# STM32H730_PINOUT.net
KiCad netlist of a schematic drawn in Altium Designer
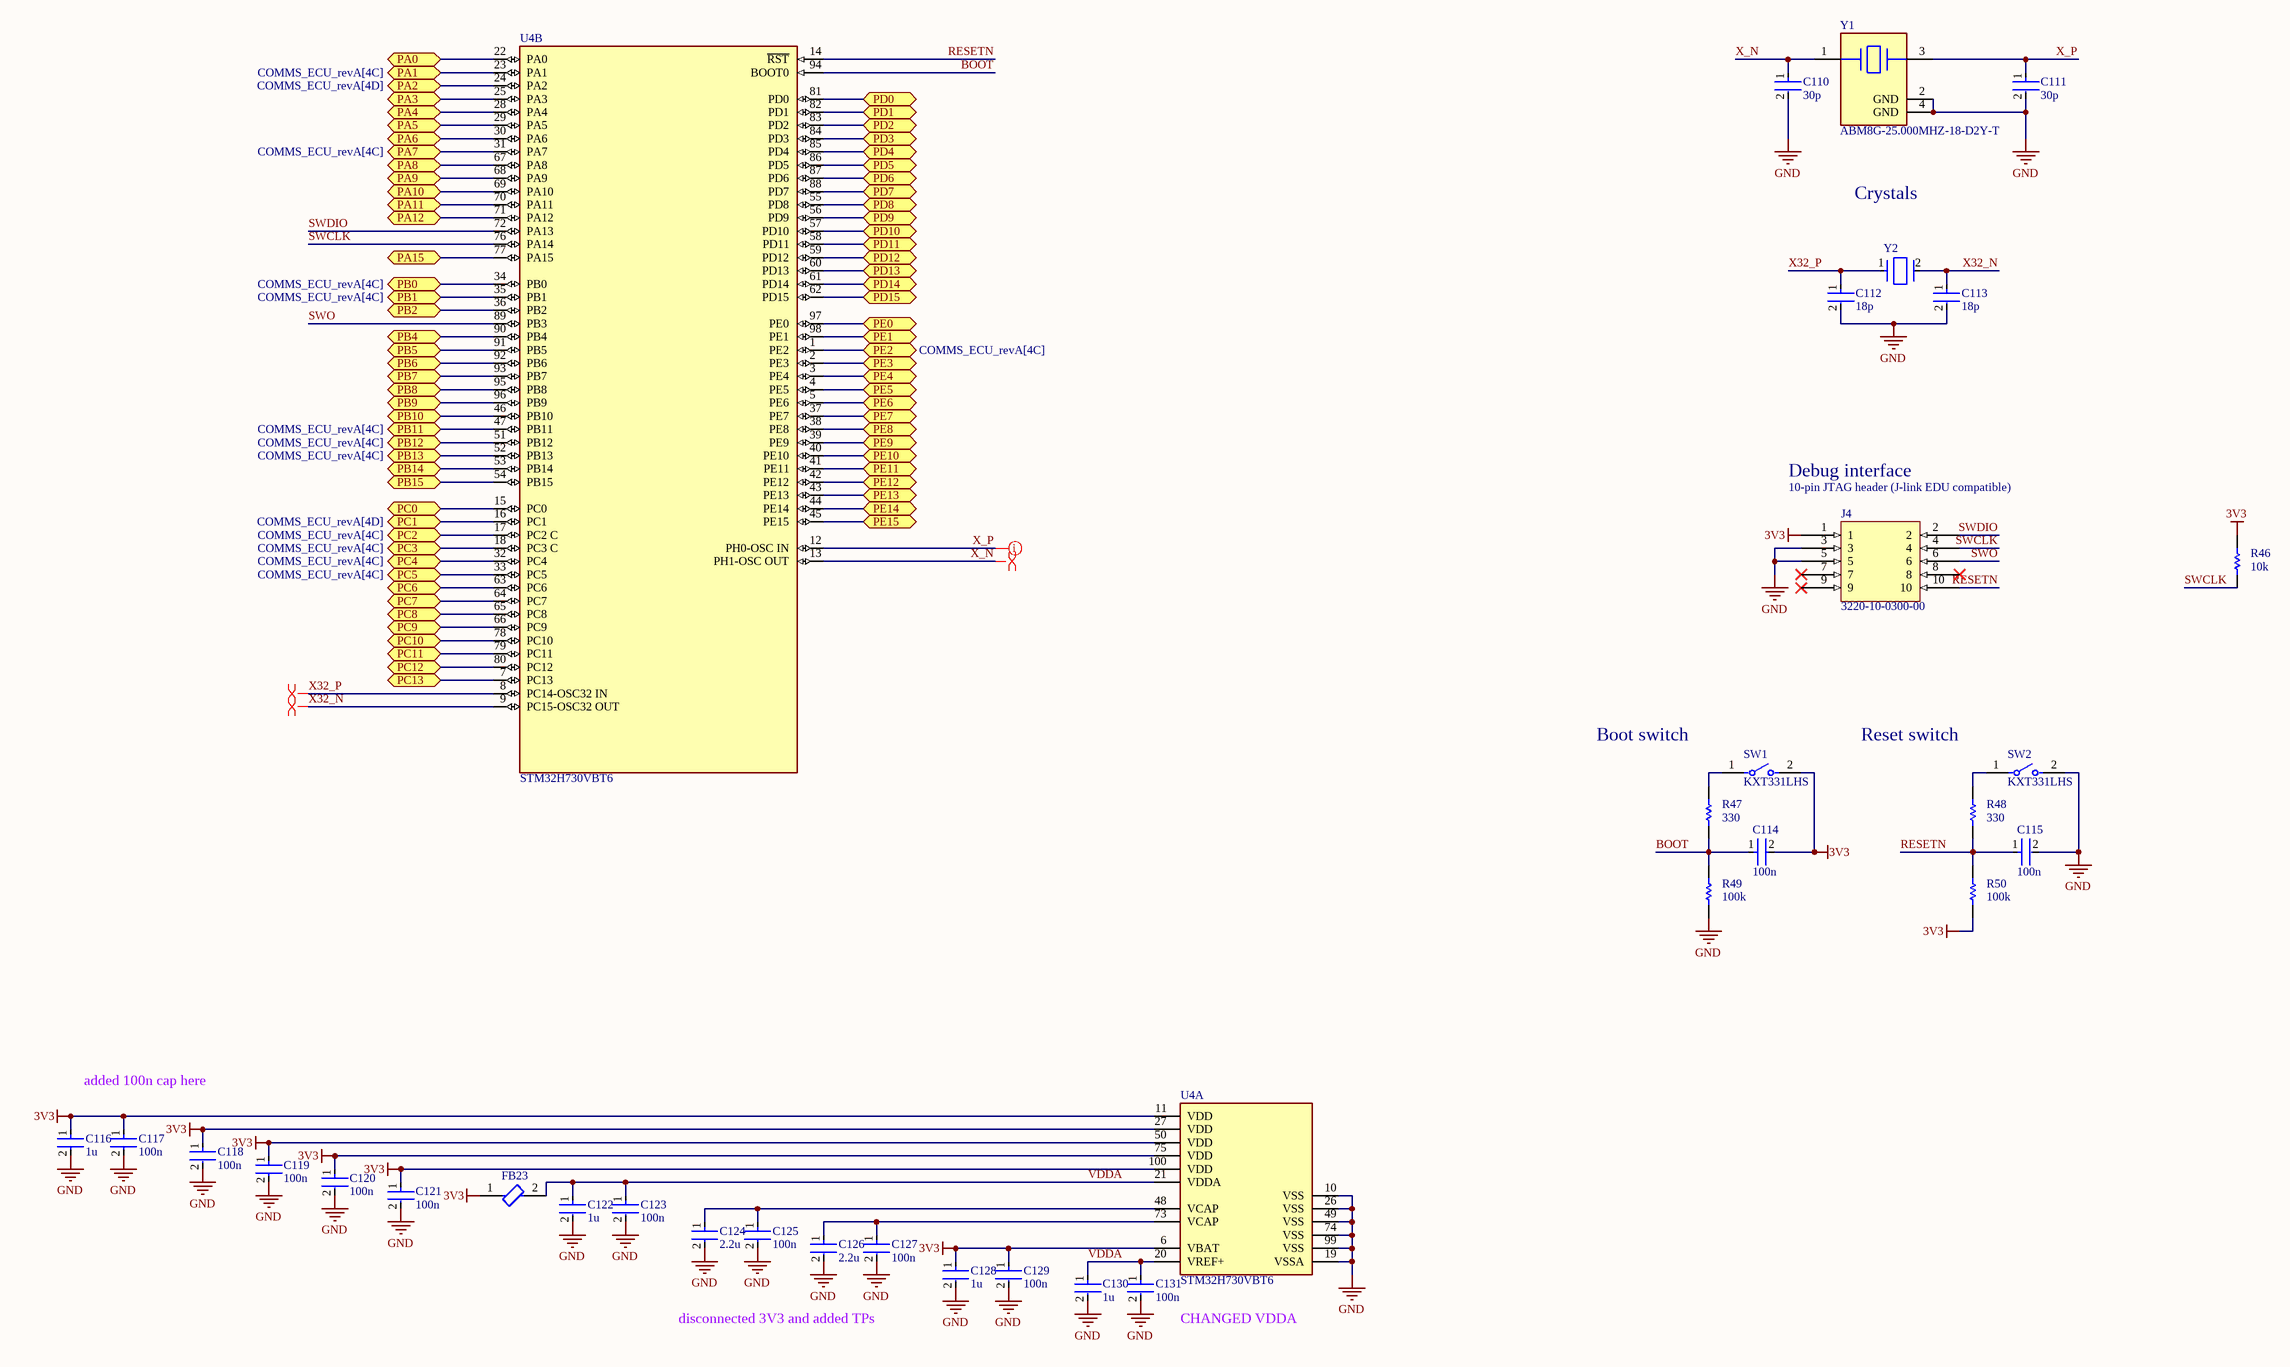
[diagram p0: STM32H730_PINOUT.SchDoc]

(export (version "E")
  (design (tool "Eeschema 10.0.6"))
  (components
    (comp (ref "C110")
      (value "30p")
      (footprint "FP-0402-L_1_0_0_05-W_0_5-IPC_A")
      (description "LARGE PADS, 0402 CAP, CHANGE COMMENT TO MATCH REAL P/N")
      (libsource (lib "Space Concordia") (part "b4654b650e69147ec39a6b967a45e02"))
    )
    (comp (ref "C111")
      (value "30p")
      (footprint "FP-0402-L_1_0_0_05-W_0_5-IPC_A")
      (description "LARGE PADS, 0402 CAP, CHANGE COMMENT TO MATCH REAL P/N")
      (libsource (lib "Space Concordia") (part "b4654b650e69147ec39a6b967a45e02"))
    )
    (comp (ref "C112")
      (value "18p")
      (footprint "FP-0402-L_1_0_0_05-W_0_5-IPC_A")
      (description "LARGE PADS, 0402 CAP, CHANGE COMMENT TO MATCH REAL P/N")
      (libsource (lib "Space Concordia") (part "b4654b650e69147ec39a6b967a45e02"))
    )
    (comp (ref "C113")
      (value "18p")
      (footprint "FP-0402-L_1_0_0_05-W_0_5-IPC_A")
      (description "LARGE PADS, 0402 CAP, CHANGE COMMENT TO MATCH REAL P/N")
      (libsource (lib "Space Concordia") (part "b4654b650e69147ec39a6b967a45e02"))
    )
    (comp (ref "C114")
      (value "100n")
      (footprint "FP-0402-L_1_0_0_05-W_0_5-IPC_A")
      (description "LARGE PADS, 0402 CAP, CHANGE COMMENT TO MATCH REAL P/N")
      (libsource (lib "Space Concordia") (part "b4654b650e69147ec39a6b967a45e02"))
    )
    (comp (ref "C115")
      (value "100n")
      (footprint "FP-0402-L_1_0_0_05-W_0_5-IPC_A")
      (description "LARGE PADS, 0402 CAP, CHANGE COMMENT TO MATCH REAL P/N")
      (libsource (lib "Space Concordia") (part "b4654b650e69147ec39a6b967a45e02"))
    )
    (comp (ref "C116")
      (value "1u")
      (footprint "FP-0402-L_1_0_0_05-W_0_5-IPC_A")
      (description "LARGE PADS, 0402 CAP, CHANGE COMMENT TO MATCH REAL P/N")
      (libsource (lib "Space Concordia") (part "b4654b650e69147ec39a6b967a45e02"))
    )
    (comp (ref "C117")
      (value "100n")
      (footprint "FP-0402-L_1_0_0_05-W_0_5-IPC_A")
      (description "LARGE PADS, 0402 CAP, CHANGE COMMENT TO MATCH REAL P/N")
      (libsource (lib "Space Concordia") (part "b4654b650e69147ec39a6b967a45e02"))
    )
    (comp (ref "C118")
      (value "100n")
      (footprint "FP-0402-L_1_0_0_05-W_0_5-IPC_A")
      (description "LARGE PADS, 0402 CAP, CHANGE COMMENT TO MATCH REAL P/N")
      (libsource (lib "Space Concordia") (part "b4654b650e69147ec39a6b967a45e02"))
    )
    (comp (ref "C119")
      (value "100n")
      (footprint "FP-0402-L_1_0_0_05-W_0_5-IPC_A")
      (description "LARGE PADS, 0402 CAP, CHANGE COMMENT TO MATCH REAL P/N")
      (libsource (lib "Space Concordia") (part "b4654b650e69147ec39a6b967a45e02"))
    )
    (comp (ref "C120")
      (value "100n")
      (footprint "FP-0402-L_1_0_0_05-W_0_5-IPC_A")
      (description "LARGE PADS, 0402 CAP, CHANGE COMMENT TO MATCH REAL P/N")
      (libsource (lib "Space Concordia") (part "b4654b650e69147ec39a6b967a45e02"))
    )
    (comp (ref "C121")
      (value "100n")
      (footprint "FP-0402-L_1_0_0_05-W_0_5-IPC_A")
      (description "LARGE PADS, 0402 CAP, CHANGE COMMENT TO MATCH REAL P/N")
      (libsource (lib "Space Concordia") (part "b4654b650e69147ec39a6b967a45e02"))
    )
    (comp (ref "C122")
      (value "1u")
      (footprint "FP-0402-L_1_0_0_05-W_0_5-IPC_A")
      (description "LARGE PADS, 0402 CAP, CHANGE COMMENT TO MATCH REAL P/N")
      (libsource (lib "Space Concordia") (part "b4654b650e69147ec39a6b967a45e02"))
    )
    (comp (ref "C123")
      (value "100n")
      (footprint "FP-0402-L_1_0_0_05-W_0_5-IPC_A")
      (description "LARGE PADS, 0402 CAP, CHANGE COMMENT TO MATCH REAL P/N")
      (libsource (lib "Space Concordia") (part "b4654b650e69147ec39a6b967a45e02"))
    )
    (comp (ref "C124")
      (value "2.2u")
      (footprint "FP-0402-L_1_0_0_05-W_0_5-IPC_A")
      (description "LARGE PADS, 0402 CAP, CHANGE COMMENT TO MATCH REAL P/N")
      (libsource (lib "Space Concordia") (part "b4654b650e69147ec39a6b967a45e02"))
    )
    (comp (ref "C125")
      (value "100n")
      (footprint "FP-0402-L_1_0_0_05-W_0_5-IPC_A")
      (description "LARGE PADS, 0402 CAP, CHANGE COMMENT TO MATCH REAL P/N")
      (libsource (lib "Space Concordia") (part "b4654b650e69147ec39a6b967a45e02"))
    )
    (comp (ref "C126")
      (value "2.2u")
      (footprint "FP-0402-L_1_0_0_05-W_0_5-IPC_A")
      (description "LARGE PADS, 0402 CAP, CHANGE COMMENT TO MATCH REAL P/N")
      (libsource (lib "Space Concordia") (part "b4654b650e69147ec39a6b967a45e02"))
    )
    (comp (ref "C127")
      (value "100n")
      (footprint "FP-0402-L_1_0_0_05-W_0_5-IPC_A")
      (description "LARGE PADS, 0402 CAP, CHANGE COMMENT TO MATCH REAL P/N")
      (libsource (lib "Space Concordia") (part "b4654b650e69147ec39a6b967a45e02"))
    )
    (comp (ref "C128")
      (value "1u")
      (footprint "FP-0402-L_1_0_0_05-W_0_5-IPC_A")
      (description "LARGE PADS, 0402 CAP, CHANGE COMMENT TO MATCH REAL P/N")
      (libsource (lib "Space Concordia") (part "b4654b650e69147ec39a6b967a45e02"))
    )
    (comp (ref "C129")
      (value "100n")
      (footprint "FP-0402-L_1_0_0_05-W_0_5-IPC_A")
      (description "LARGE PADS, 0402 CAP, CHANGE COMMENT TO MATCH REAL P/N")
      (libsource (lib "Space Concordia") (part "b4654b650e69147ec39a6b967a45e02"))
    )
    (comp (ref "C130")
      (value "1u")
      (footprint "FP-0402-L_1_0_0_05-W_0_5-IPC_A")
      (description "LARGE PADS, 0402 CAP, CHANGE COMMENT TO MATCH REAL P/N")
      (libsource (lib "Space Concordia") (part "b4654b650e69147ec39a6b967a45e02"))
    )
    (comp (ref "C131")
      (value "100n")
      (footprint "FP-0402-L_1_0_0_05-W_0_5-IPC_A")
      (description "LARGE PADS, 0402 CAP, CHANGE COMMENT TO MATCH REAL P/N")
      (libsource (lib "Space Concordia") (part "b4654b650e69147ec39a6b967a45e02"))
    )
    (comp (ref "FB23")
      (value "BLM15PX601SN1D")
      (footprint "FP-BLM15-0_05-IPC_A")
      (description "Chip Ferrite Bead, 0402, 600Ω @ 100MHz, 0.23Ω, 25%, 900mA")
      (fields (field (name "TOLERANCE") "25%"))
      (libsource (lib "Altium Content Vault") (part "5f30dd21d616792df468990f7003faa"))
    )
    (comp (ref "J4")
      (value "3220-10-0300-00")
      (footprint "3220-10-0300-00-Footprint-1")
      (description "CONN HEADER SMD 10POS 1.27MM")
      (libsource (lib "Space Concordia") (part "3220-10-0300-00"))
    )
    (comp (ref "R46")
      (value "10k")
      (footprint "R0603B")
      (description "Resistor")
      (libsource (lib "Space Concordia") (part "Resistor"))
    )
    (comp (ref "R47")
      (value "330")
      (footprint "R0603B")
      (description "Resistor")
      (libsource (lib "Space Concordia") (part "Resistor"))
    )
    (comp (ref "R48")
      (value "330")
      (footprint "R0603B")
      (description "Resistor")
      (libsource (lib "Space Concordia") (part "Resistor"))
    )
    (comp (ref "R49")
      (value "100k")
      (footprint "R0603B")
      (description "Resistor")
      (libsource (lib "Space Concordia") (part "Resistor"))
    )
    (comp (ref "R50")
      (value "100k")
      (footprint "R0603B")
      (description "Resistor")
      (libsource (lib "Space Concordia") (part "Resistor"))
    )
    (comp (ref "SW1")
      (value "KXT331LHS")
      (footprint "FP-KXT331LHS-MFG")
      (description "SWITCH TACTILE SPST-NO 0.02A 15V")
      (libsource (lib "Altium Content Vault") (part "bb27bde45df87f1f469753f287ef5ae"))
    )
    (comp (ref "SW2")
      (value "KXT331LHS")
      (footprint "FP-KXT331LHS-MFG")
      (description "SWITCH TACTILE SPST-NO 0.02A 15V")
      (libsource (lib "Altium Content Vault") (part "bb27bde45df87f1f469753f287ef5ae"))
    )
    (comp (ref "U4")
      (value "STM32H730VBT6")
      (footprint "FP-LQFP100-1L-IPC_C")
      (description "IC MCU 32BIT 128KB FLASH 100LQFP")
      (libsource (lib "Altium Content Vault") (part "44dc6501260a4d92b846760feb66c20"))
    )
    (comp (ref "Y1")
      (value "ABM8G-25.000MHZ-18-D2Y-T")
      (footprint "FP-ABM8G-MFG")
      (description "Crystal 25MHz ±20ppm (Tol) ±30ppm (Stability) 18pF FUND 60Ω 4-Pin SMD T/R")
      (fields (field (name "TOLERANCE") "20ppm"))
      (libsource (lib "Altium Content Vault") (part "48e526d86b7f2615d98721063c72f49"))
    )
    (comp (ref "Y2")
      (value "ECS-.327-12.5-1210-TR")
      (footprint "FP-ECX-1210-MFG")
      (description "CRYSTAL 32.7680KHZ 12.5PF SMD")
      (fields
        (field (name "OCTOPART") "https://octopart.com/ecs-.327-12.5-1210-tr-ecs+international-81221340")
        (field (name "TOLERANCE") "20ppm")
      )
      (libsource (lib "Altium Content Vault") (part "99724985039315a44fd0d1401b84e49"))
    )
  )
  (nets
    (net (code "1") (name "/BOOT") (class "Default")
      (node (ref "C114") (pin "1") (pinfunction "1_1") (pintype "passive"))
      (node (ref "R47") (pin "1") (pinfunction "1_1") (pintype "passive"))
      (node (ref "R49") (pin "2") (pinfunction "2_2") (pintype "passive"))
      (node (ref "U4") (pin "94") (pinfunction "BOOT0_94") (pintype "input"))
    )
    (net (code "2") (name "/PA0") (class "Default")
      (node (ref "U4") (pin "22") (pinfunction "PA0_22") (pintype "bidirectional"))
    )
    (net (code "3") (name "/PA1") (class "Default")
      (node (ref "U4") (pin "23") (pinfunction "PA1_23") (pintype "bidirectional"))
    )
    (net (code "4") (name "/PA2") (class "Default")
      (node (ref "U4") (pin "24") (pinfunction "PA2_24") (pintype "bidirectional"))
    )
    (net (code "5") (name "/PA3") (class "Default")
      (node (ref "U4") (pin "25") (pinfunction "PA3_25") (pintype "bidirectional"))
    )
    (net (code "6") (name "/PA4") (class "Default")
      (node (ref "U4") (pin "28") (pinfunction "PA4_28") (pintype "bidirectional"))
    )
    (net (code "7") (name "/PA5") (class "Default")
      (node (ref "U4") (pin "29") (pinfunction "PA5_29") (pintype "bidirectional"))
    )
    (net (code "8") (name "/PA6") (class "Default")
      (node (ref "U4") (pin "30") (pinfunction "PA6_30") (pintype "bidirectional"))
    )
    (net (code "9") (name "/PA7") (class "Default")
      (node (ref "U4") (pin "31") (pinfunction "PA7_31") (pintype "bidirectional"))
    )
    (net (code "10") (name "/PA8") (class "Default")
      (node (ref "U4") (pin "67") (pinfunction "PA8_67") (pintype "bidirectional"))
    )
    (net (code "11") (name "/PA9") (class "Default")
      (node (ref "U4") (pin "68") (pinfunction "PA9_68") (pintype "bidirectional"))
    )
    (net (code "12") (name "/PA10") (class "Default")
      (node (ref "U4") (pin "69") (pinfunction "PA10_69") (pintype "bidirectional"))
    )
    (net (code "13") (name "/PA11") (class "Default")
      (node (ref "U4") (pin "70") (pinfunction "PA11_70") (pintype "bidirectional"))
    )
    (net (code "14") (name "/PA12") (class "Default")
      (node (ref "U4") (pin "71") (pinfunction "PA12_71") (pintype "bidirectional"))
    )
    (net (code "15") (name "/PA15") (class "Default")
      (node (ref "U4") (pin "77") (pinfunction "PA15_77") (pintype "bidirectional"))
    )
    (net (code "16") (name "/PB0") (class "Default")
      (node (ref "U4") (pin "34") (pinfunction "PB0_34") (pintype "bidirectional"))
    )
    (net (code "17") (name "/PB1") (class "Default")
      (node (ref "U4") (pin "35") (pinfunction "PB1_35") (pintype "bidirectional"))
    )
    (net (code "18") (name "/PB2") (class "Default")
      (node (ref "U4") (pin "36") (pinfunction "PB2_36") (pintype "bidirectional"))
    )
    (net (code "19") (name "/PB4") (class "Default")
      (node (ref "U4") (pin "90") (pinfunction "PB4_90") (pintype "bidirectional"))
    )
    (net (code "20") (name "/PB5") (class "Default")
      (node (ref "U4") (pin "91") (pinfunction "PB5_91") (pintype "bidirectional"))
    )
    (net (code "21") (name "/PB6") (class "Default")
      (node (ref "U4") (pin "92") (pinfunction "PB6_92") (pintype "bidirectional"))
    )
    (net (code "22") (name "/PB7") (class "Default")
      (node (ref "U4") (pin "93") (pinfunction "PB7_93") (pintype "bidirectional"))
    )
    (net (code "23") (name "/PB8") (class "Default")
      (node (ref "U4") (pin "95") (pinfunction "PB8_95") (pintype "bidirectional"))
    )
    (net (code "24") (name "/PB9") (class "Default")
      (node (ref "U4") (pin "96") (pinfunction "PB9_96") (pintype "bidirectional"))
    )
    (net (code "25") (name "/PB10") (class "Default")
      (node (ref "U4") (pin "46") (pinfunction "PB10_46") (pintype "bidirectional"))
    )
    (net (code "26") (name "/PB11") (class "Default")
      (node (ref "U4") (pin "47") (pinfunction "PB11_47") (pintype "bidirectional"))
    )
    (net (code "27") (name "/PB12") (class "Default")
      (node (ref "U4") (pin "51") (pinfunction "PB12_51") (pintype "bidirectional"))
    )
    (net (code "28") (name "/PB13") (class "Default")
      (node (ref "U4") (pin "52") (pinfunction "PB13_52") (pintype "bidirectional"))
    )
    (net (code "29") (name "/PB14") (class "Default")
      (node (ref "U4") (pin "53") (pinfunction "PB14_53") (pintype "bidirectional"))
    )
    (net (code "30") (name "/PB15") (class "Default")
      (node (ref "U4") (pin "54") (pinfunction "PB15_54") (pintype "bidirectional"))
    )
    (net (code "31") (name "/PC0") (class "Default")
      (node (ref "U4") (pin "15") (pinfunction "PC0_15") (pintype "bidirectional"))
    )
    (net (code "32") (name "/PC1") (class "Default")
      (node (ref "U4") (pin "16") (pinfunction "PC1_16") (pintype "bidirectional"))
    )
    (net (code "33") (name "/PC2") (class "Default")
      (node (ref "U4") (pin "17") (pinfunction "PC2_C_17") (pintype "bidirectional"))
    )
    (net (code "34") (name "/PC3") (class "Default")
      (node (ref "U4") (pin "18") (pinfunction "PC3_C_18") (pintype "bidirectional"))
    )
    (net (code "35") (name "/PC4") (class "Default")
      (node (ref "U4") (pin "32") (pinfunction "PC4_32") (pintype "bidirectional"))
    )
    (net (code "36") (name "/PC5") (class "Default")
      (node (ref "U4") (pin "33") (pinfunction "PC5_33") (pintype "bidirectional"))
    )
    (net (code "37") (name "/PC6") (class "Default")
      (node (ref "U4") (pin "63") (pinfunction "PC6_63") (pintype "bidirectional"))
    )
    (net (code "38") (name "/PC7") (class "Default")
      (node (ref "U4") (pin "64") (pinfunction "PC7_64") (pintype "bidirectional"))
    )
    (net (code "39") (name "/PC8") (class "Default")
      (node (ref "U4") (pin "65") (pinfunction "PC8_65") (pintype "bidirectional"))
    )
    (net (code "40") (name "/PC9") (class "Default")
      (node (ref "U4") (pin "66") (pinfunction "PC9_66") (pintype "bidirectional"))
    )
    (net (code "41") (name "/PC10") (class "Default")
      (node (ref "U4") (pin "78") (pinfunction "PC10_78") (pintype "bidirectional"))
    )
    (net (code "42") (name "/PC11") (class "Default")
      (node (ref "U4") (pin "79") (pinfunction "PC11_79") (pintype "bidirectional"))
    )
    (net (code "43") (name "/PC12") (class "Default")
      (node (ref "U4") (pin "80") (pinfunction "PC12_80") (pintype "bidirectional"))
    )
    (net (code "44") (name "/PC13") (class "Default")
      (node (ref "U4") (pin "7") (pinfunction "PC13_7") (pintype "bidirectional"))
    )
    (net (code "45") (name "/PD0") (class "Default")
      (node (ref "U4") (pin "81") (pinfunction "PD0_81") (pintype "bidirectional"))
    )
    (net (code "46") (name "/PD1") (class "Default")
      (node (ref "U4") (pin "82") (pinfunction "PD1_82") (pintype "bidirectional"))
    )
    (net (code "47") (name "/PD2") (class "Default")
      (node (ref "U4") (pin "83") (pinfunction "PD2_83") (pintype "bidirectional"))
    )
    (net (code "48") (name "/PD3") (class "Default")
      (node (ref "U4") (pin "84") (pinfunction "PD3_84") (pintype "bidirectional"))
    )
    (net (code "49") (name "/PD4") (class "Default")
      (node (ref "U4") (pin "85") (pinfunction "PD4_85") (pintype "bidirectional"))
    )
    (net (code "50") (name "/PD5") (class "Default")
      (node (ref "U4") (pin "86") (pinfunction "PD5_86") (pintype "bidirectional"))
    )
    (net (code "51") (name "/PD6") (class "Default")
      (node (ref "U4") (pin "87") (pinfunction "PD6_87") (pintype "bidirectional"))
    )
    (net (code "52") (name "/PD7") (class "Default")
      (node (ref "U4") (pin "88") (pinfunction "PD7_88") (pintype "bidirectional"))
    )
    (net (code "53") (name "/PD8") (class "Default")
      (node (ref "U4") (pin "55") (pinfunction "PD8_55") (pintype "bidirectional"))
    )
    (net (code "54") (name "/PD9") (class "Default")
      (node (ref "U4") (pin "56") (pinfunction "PD9_56") (pintype "bidirectional"))
    )
    (net (code "55") (name "/PD10") (class "Default")
      (node (ref "U4") (pin "57") (pinfunction "PD10_57") (pintype "bidirectional"))
    )
    (net (code "56") (name "/PD11") (class "Default")
      (node (ref "U4") (pin "58") (pinfunction "PD11_58") (pintype "bidirectional"))
    )
    (net (code "57") (name "/PD12") (class "Default")
      (node (ref "U4") (pin "59") (pinfunction "PD12_59") (pintype "bidirectional"))
    )
    (net (code "58") (name "/PD13") (class "Default")
      (node (ref "U4") (pin "60") (pinfunction "PD13_60") (pintype "bidirectional"))
    )
    (net (code "59") (name "/PD14") (class "Default")
      (node (ref "U4") (pin "61") (pinfunction "PD14_61") (pintype "bidirectional"))
    )
    (net (code "60") (name "/PD15") (class "Default")
      (node (ref "U4") (pin "62") (pinfunction "PD15_62") (pintype "bidirectional"))
    )
    (net (code "61") (name "/PE0") (class "Default")
      (node (ref "U4") (pin "97") (pinfunction "PE0_97") (pintype "bidirectional"))
    )
    (net (code "62") (name "/PE1") (class "Default")
      (node (ref "U4") (pin "98") (pinfunction "PE1_98") (pintype "bidirectional"))
    )
    (net (code "63") (name "/PE2") (class "Default")
      (node (ref "U4") (pin "1") (pinfunction "PE2_1") (pintype "bidirectional"))
    )
    (net (code "64") (name "/PE3") (class "Default")
      (node (ref "U4") (pin "2") (pinfunction "PE3_2") (pintype "bidirectional"))
    )
    (net (code "65") (name "/PE4") (class "Default")
      (node (ref "U4") (pin "3") (pinfunction "PE4_3") (pintype "bidirectional"))
    )
    (net (code "66") (name "/PE5") (class "Default")
      (node (ref "U4") (pin "4") (pinfunction "PE5_4") (pintype "bidirectional"))
    )
    (net (code "67") (name "/PE6") (class "Default")
      (node (ref "U4") (pin "5") (pinfunction "PE6_5") (pintype "bidirectional"))
    )
    (net (code "68") (name "/PE7") (class "Default")
      (node (ref "U4") (pin "37") (pinfunction "PE7_37") (pintype "bidirectional"))
    )
    (net (code "69") (name "/PE8") (class "Default")
      (node (ref "U4") (pin "38") (pinfunction "PE8_38") (pintype "bidirectional"))
    )
    (net (code "70") (name "/PE9") (class "Default")
      (node (ref "U4") (pin "39") (pinfunction "PE9_39") (pintype "bidirectional"))
    )
    (net (code "71") (name "/PE10") (class "Default")
      (node (ref "U4") (pin "40") (pinfunction "PE10_40") (pintype "bidirectional"))
    )
    (net (code "72") (name "/PE11") (class "Default")
      (node (ref "U4") (pin "41") (pinfunction "PE11_41") (pintype "bidirectional"))
    )
    (net (code "73") (name "/PE12") (class "Default")
      (node (ref "U4") (pin "42") (pinfunction "PE12_42") (pintype "bidirectional"))
    )
    (net (code "74") (name "/PE13") (class "Default")
      (node (ref "U4") (pin "43") (pinfunction "PE13_43") (pintype "bidirectional"))
    )
    (net (code "75") (name "/PE14") (class "Default")
      (node (ref "U4") (pin "44") (pinfunction "PE14_44") (pintype "bidirectional"))
    )
    (net (code "76") (name "/PE15") (class "Default")
      (node (ref "U4") (pin "45") (pinfunction "PE15_45") (pintype "bidirectional"))
    )
    (net (code "77") (name "/RESETN") (class "Default")
      (node (ref "C115") (pin "1") (pinfunction "1_1") (pintype "passive"))
      (node (ref "J4") (pin "10") (pinfunction "10_10") (pintype "input"))
      (node (ref "R48") (pin "1") (pinfunction "1_1") (pintype "passive"))
      (node (ref "R50") (pin "2") (pinfunction "2_2") (pintype "passive"))
      (node (ref "U4") (pin "14") (pinfunction "~{RST}_14") (pintype "input"))
    )
    (net (code "78") (name "/SWCLK") (class "Default")
      (node (ref "J4") (pin "4") (pinfunction "4_4") (pintype "input"))
      (node (ref "R46") (pin "1") (pinfunction "1_1") (pintype "passive"))
      (node (ref "U4") (pin "76") (pinfunction "PA14_76") (pintype "bidirectional"))
    )
    (net (code "79") (name "/SWDIO") (class "Default")
      (node (ref "J4") (pin "2") (pinfunction "2_2") (pintype "input"))
      (node (ref "U4") (pin "72") (pinfunction "PA13_72") (pintype "bidirectional"))
    )
    (net (code "80") (name "/SWO") (class "Default")
      (node (ref "J4") (pin "6") (pinfunction "6_6") (pintype "input"))
      (node (ref "U4") (pin "89") (pinfunction "PB3_89") (pintype "bidirectional"))
    )
    (net (code "81") (name "/VDDA") (class "Default")
      (node (ref "C122") (pin "1") (pinfunction "1_1") (pintype "passive"))
      (node (ref "C123") (pin "1") (pinfunction "1_1") (pintype "passive"))
      (node (ref "C130") (pin "1") (pinfunction "1_1") (pintype "passive"))
      (node (ref "C131") (pin "1") (pinfunction "1_1") (pintype "passive"))
      (node (ref "FB23") (pin "2") (pinfunction "2_2") (pintype "passive"))
      (node (ref "U4") (pin "20") (pinfunction "VREF+_20") (pintype "power_in"))
      (node (ref "U4") (pin "21") (pinfunction "VDDA_21") (pintype "power_in"))
    )
    (net (code "82") (name "/X32_N") (class "Default")
      (node (ref "C113") (pin "1") (pinfunction "1_1") (pintype "passive"))
      (node (ref "U4") (pin "9") (pinfunction "PC15-OSC32_OUT_9") (pintype "bidirectional"))
      (node (ref "Y2") (pin "2") (pinfunction "Out/In_2") (pintype "passive"))
    )
    (net (code "83") (name "/X32_P") (class "Default")
      (node (ref "C112") (pin "1") (pinfunction "1_1") (pintype "passive"))
      (node (ref "U4") (pin "8") (pinfunction "PC14-OSC32_IN_8") (pintype "bidirectional"))
      (node (ref "Y2") (pin "1") (pinfunction "In/Out_1") (pintype "passive"))
    )
    (net (code "84") (name "/X_N") (class "Default")
      (node (ref "C110") (pin "1") (pinfunction "1_1") (pintype "passive"))
      (node (ref "U4") (pin "13") (pinfunction "PH1-OSC_OUT_13") (pintype "bidirectional"))
      (node (ref "Y1") (pin "1") (pinfunction "1_1") (pintype "passive"))
    )
    (net (code "85") (name "/X_P") (class "Default")
      (node (ref "C111") (pin "1") (pinfunction "1_1") (pintype "passive"))
      (node (ref "U4") (pin "12") (pinfunction "PH0-OSC_IN_12") (pintype "bidirectional"))
      (node (ref "Y1") (pin "3") (pinfunction "3_3") (pintype "passive"))
    )
    (net (code "86") (name "3V3") (class "Default")
      (node (ref "C114") (pin "2") (pinfunction "2_2") (pintype "passive"))
      (node (ref "C116") (pin "1") (pinfunction "1_1") (pintype "passive"))
      (node (ref "C117") (pin "1") (pinfunction "1_1") (pintype "passive"))
      (node (ref "C118") (pin "1") (pinfunction "1_1") (pintype "passive"))
      (node (ref "C119") (pin "1") (pinfunction "1_1") (pintype "passive"))
      (node (ref "C120") (pin "1") (pinfunction "1_1") (pintype "passive"))
      (node (ref "C121") (pin "1") (pinfunction "1_1") (pintype "passive"))
      (node (ref "C128") (pin "1") (pinfunction "1_1") (pintype "passive"))
      (node (ref "C129") (pin "1") (pinfunction "1_1") (pintype "passive"))
      (node (ref "FB23") (pin "1") (pinfunction "1_1") (pintype "passive"))
      (node (ref "J4") (pin "1") (pinfunction "1_1") (pintype "input"))
      (node (ref "R46") (pin "2") (pinfunction "2_2") (pintype "passive"))
      (node (ref "R50") (pin "1") (pinfunction "1_1") (pintype "passive"))
      (node (ref "SW1") (pin "2") (pinfunction "2_2") (pintype "passive"))
      (node (ref "U4") (pin "100") (pinfunction "VDD_100") (pintype "power_in"))
      (node (ref "U4") (pin "11") (pinfunction "VDD_11") (pintype "power_in"))
      (node (ref "U4") (pin "27") (pinfunction "VDD_27") (pintype "power_in"))
      (node (ref "U4") (pin "50") (pinfunction "VDD_50") (pintype "power_in"))
      (node (ref "U4") (pin "6") (pinfunction "VBAT_6") (pintype "power_in"))
      (node (ref "U4") (pin "75") (pinfunction "VDD_75") (pintype "power_in"))
    )
    (net (code "87") (name "GND") (class "Default")
      (node (ref "C110") (pin "2") (pinfunction "2_2") (pintype "passive"))
      (node (ref "C111") (pin "2") (pinfunction "2_2") (pintype "passive"))
      (node (ref "C112") (pin "2") (pinfunction "2_2") (pintype "passive"))
      (node (ref "C113") (pin "2") (pinfunction "2_2") (pintype "passive"))
      (node (ref "C115") (pin "2") (pinfunction "2_2") (pintype "passive"))
      (node (ref "C116") (pin "2") (pinfunction "2_2") (pintype "passive"))
      (node (ref "C117") (pin "2") (pinfunction "2_2") (pintype "passive"))
      (node (ref "C118") (pin "2") (pinfunction "2_2") (pintype "passive"))
      (node (ref "C119") (pin "2") (pinfunction "2_2") (pintype "passive"))
      (node (ref "C120") (pin "2") (pinfunction "2_2") (pintype "passive"))
      (node (ref "C121") (pin "2") (pinfunction "2_2") (pintype "passive"))
      (node (ref "C122") (pin "2") (pinfunction "2_2") (pintype "passive"))
      (node (ref "C123") (pin "2") (pinfunction "2_2") (pintype "passive"))
      (node (ref "C124") (pin "2") (pinfunction "2_2") (pintype "passive"))
      (node (ref "C125") (pin "2") (pinfunction "2_2") (pintype "passive"))
      (node (ref "C126") (pin "2") (pinfunction "2_2") (pintype "passive"))
      (node (ref "C127") (pin "2") (pinfunction "2_2") (pintype "passive"))
      (node (ref "C128") (pin "2") (pinfunction "2_2") (pintype "passive"))
      (node (ref "C129") (pin "2") (pinfunction "2_2") (pintype "passive"))
      (node (ref "C130") (pin "2") (pinfunction "2_2") (pintype "passive"))
      (node (ref "C131") (pin "2") (pinfunction "2_2") (pintype "passive"))
      (node (ref "J4") (pin "3") (pinfunction "3_3") (pintype "input"))
      (node (ref "J4") (pin "5") (pinfunction "5_5") (pintype "input"))
      (node (ref "R49") (pin "1") (pinfunction "1_1") (pintype "passive"))
      (node (ref "SW2") (pin "2") (pinfunction "2_2") (pintype "passive"))
      (node (ref "U4") (pin "10") (pinfunction "VSS_10") (pintype "power_in"))
      (node (ref "U4") (pin "19") (pinfunction "VSSA_19") (pintype "power_in"))
      (node (ref "U4") (pin "26") (pinfunction "VSS_26") (pintype "power_in"))
      (node (ref "U4") (pin "49") (pinfunction "VSS_49") (pintype "power_in"))
      (node (ref "U4") (pin "74") (pinfunction "VSS_74") (pintype "power_in"))
      (node (ref "U4") (pin "99") (pinfunction "VSS_99") (pintype "power_in"))
      (node (ref "Y1") (pin "2") (pinfunction "GND_2") (pintype "power_in"))
      (node (ref "Y1") (pin "4") (pinfunction "GND_4") (pintype "power_in"))
    )
    (net (code "88") (name "Net-(C124-Pad1)") (class "Default")
      (node (ref "C124") (pin "1") (pinfunction "1_1") (pintype "passive"))
      (node (ref "C125") (pin "1") (pinfunction "1_1") (pintype "passive"))
      (node (ref "U4") (pin "48") (pinfunction "VCAP_48") (pintype "power_in"))
    )
    (net (code "89") (name "Net-(C126-Pad1)") (class "Default")
      (node (ref "C126") (pin "1") (pinfunction "1_1") (pintype "passive"))
      (node (ref "C127") (pin "1") (pinfunction "1_1") (pintype "passive"))
      (node (ref "U4") (pin "73") (pinfunction "VCAP_73") (pintype "power_in"))
    )
    (net (code "90") (name "Net-(R47-Pad2)") (class "Default")
      (node (ref "R47") (pin "2") (pinfunction "2_2") (pintype "passive"))
      (node (ref "SW1") (pin "1") (pinfunction "1_1") (pintype "passive"))
    )
    (net (code "91") (name "Net-(R48-Pad2)") (class "Default")
      (node (ref "R48") (pin "2") (pinfunction "2_2") (pintype "passive"))
      (node (ref "SW2") (pin "1") (pinfunction "1_1") (pintype "passive"))
    )
    (net (code "92") (name "unconnected-(J4-Pad7)") (class "Default")
      (node (ref "J4") (pin "7") (pinfunction "7_7") (pintype "input+no_connect"))
    )
    (net (code "93") (name "unconnected-(J4-Pad8)") (class "Default")
      (node (ref "J4") (pin "8") (pinfunction "8_8") (pintype "input+no_connect"))
    )
    (net (code "94") (name "unconnected-(J4-Pad9)") (class "Default")
      (node (ref "J4") (pin "9") (pinfunction "9_9") (pintype "input+no_connect"))
    )
  )
)
